# PULL.net
KiCad netlist of a schematic drawn in Altium Designer
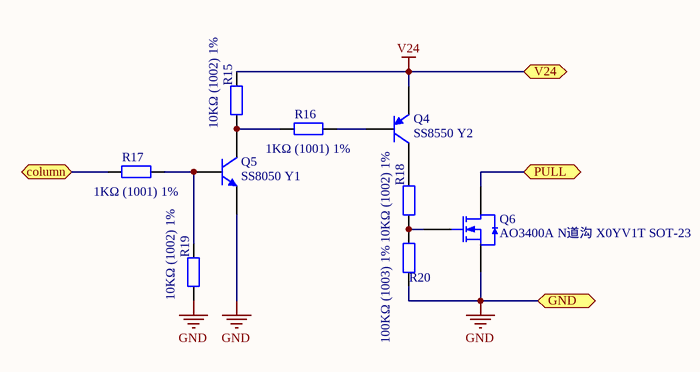
[diagram p0: PULL.SchDoc]

(export (version "E")
  (design (tool "Eeschema 10.0.6"))
  (components
    (comp (ref "Q4")
      (value "SS8550 Y2")
      (footprint "SOT-23(SOT-23-3)")
      (description "三极管")
      (libsource (lib "Miscellaneous Devices LC") (part "SOT-23 SS8550 Y2"))
    )
    (comp (ref "Q5")
      (value "SS8050 Y1")
      (footprint "SOT-23(SOT-23-3)")
      (description "三极管")
      (libsource (lib "Miscellaneous Devices LC") (part "SOT-23 SS8050 Y1"))
    )
    (comp (ref "Q6")
      (value "AO3400A N道沟 X0YV1T SOT-23")
      (footprint "SOT-23-3L")
      (description "MOS(场效应管)")
      (libsource (lib "Miscellaneous Devices LC") (part "AO3400A N道沟 X0YV1T SOT-23"))
    )
    (comp (ref "R15")
      (value "10KΩ (1002) 1%")
      (footprint "0805_R")
      (description "贴片电阻")
      (libsource (lib "Miscellaneous Devices LC") (part "0805 10KΩ (1002) 1%"))
    )
    (comp (ref "R16")
      (value "1KΩ (1001) 1%")
      (footprint "0805_R")
      (description "贴片电阻")
      (libsource (lib "Miscellaneous Devices LC") (part "0805 1KΩ (1001) 1%"))
    )
    (comp (ref "R17")
      (value "1KΩ (1001) 1%")
      (footprint "0805_R")
      (description "贴片电阻")
      (libsource (lib "Miscellaneous Devices LC") (part "0805 1KΩ (1001) 1%"))
    )
    (comp (ref "R18")
      (value "10KΩ (1002) 1%")
      (footprint "0805_R")
      (description "贴片电阻")
      (libsource (lib "Miscellaneous Devices LC") (part "0805 10KΩ (1002) 1%"))
    )
    (comp (ref "R19")
      (value "10KΩ (1002) 1%")
      (footprint "0805_R")
      (description "贴片电阻")
      (libsource (lib "Miscellaneous Devices LC") (part "0805 10KΩ (1002) 1%"))
    )
    (comp (ref "R20")
      (value "100KΩ (1003) 1%")
      (footprint "0805_R")
      (description "贴片电阻")
      (libsource (lib "Miscellaneous Devices LC") (part "0805 100KΩ (1003) 1%"))
    )
  )
  (nets
    (net (code "1") (name "/PULL") (class "Default")
      (node (ref "Q6") (pin "3") (pinfunction "D_3") (pintype "passive"))
    )
    (net (code "2") (name "/column") (class "Default")
      (node (ref "R17") (pin "2") (pinfunction "2_2") (pintype "passive"))
    )
    (net (code "3") (name "GND") (class "Default")
      (node (ref "Q5") (pin "2") (pinfunction "E_2") (pintype "passive"))
      (node (ref "Q6") (pin "2") (pinfunction "S_2") (pintype "passive"))
      (node (ref "R19") (pin "1") (pinfunction "1_1") (pintype "passive"))
      (node (ref "R20") (pin "2") (pinfunction "2_2") (pintype "passive"))
    )
    (net (code "4") (name "Net-(Q4-B)") (class "Default")
      (node (ref "Q4") (pin "1") (pinfunction "B_1") (pintype "passive"))
      (node (ref "R16") (pin "1") (pinfunction "1_1") (pintype "passive"))
    )
    (net (code "5") (name "Net-(Q4-C)") (class "Default")
      (node (ref "Q4") (pin "3") (pinfunction "C_3") (pintype "passive"))
      (node (ref "R18") (pin "2") (pinfunction "2_2") (pintype "passive"))
    )
    (net (code "6") (name "Net-(Q5-B)") (class "Default")
      (node (ref "Q5") (pin "1") (pinfunction "B_1") (pintype "passive"))
      (node (ref "R17") (pin "1") (pinfunction "1_1") (pintype "passive"))
      (node (ref "R19") (pin "2") (pinfunction "2_2") (pintype "passive"))
    )
    (net (code "7") (name "Net-(Q5-C)") (class "Default")
      (node (ref "Q5") (pin "3") (pinfunction "C_3") (pintype "passive"))
      (node (ref "R15") (pin "1") (pinfunction "1_1") (pintype "passive"))
      (node (ref "R16") (pin "2") (pinfunction "2_2") (pintype "passive"))
    )
    (net (code "8") (name "Net-(Q6-G)") (class "Default")
      (node (ref "Q6") (pin "1") (pinfunction "G_1") (pintype "passive"))
      (node (ref "R18") (pin "1") (pinfunction "1_1") (pintype "passive"))
      (node (ref "R20") (pin "1") (pinfunction "1_1") (pintype "passive"))
    )
    (net (code "9") (name "V24") (class "Default")
      (node (ref "Q4") (pin "2") (pinfunction "E_2") (pintype "passive"))
      (node (ref "R15") (pin "2") (pinfunction "2_2") (pintype "passive"))
    )
  )
)
